# opamp_bandpass.net
KiCad netlist of a schematic drawn in EAGLE
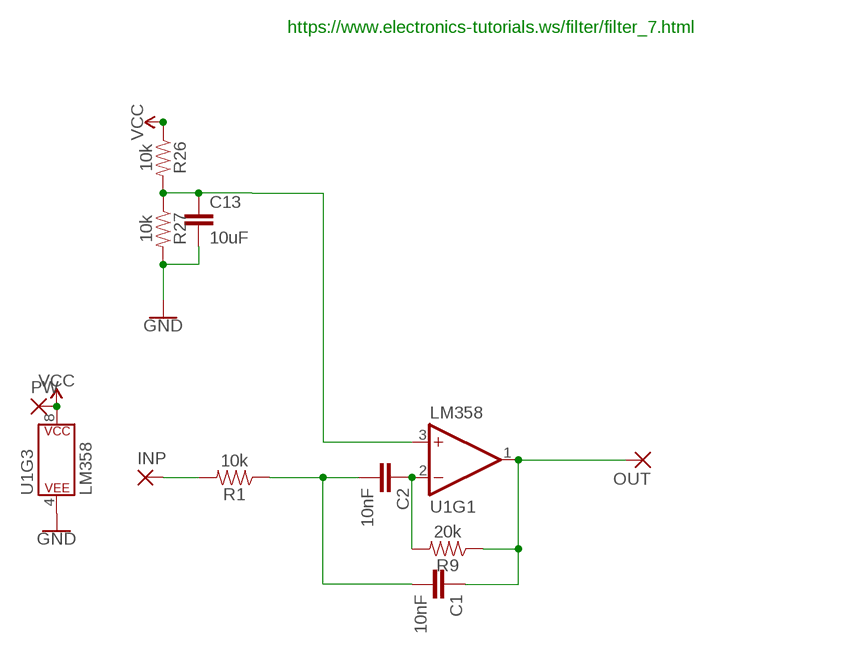
[diagram p0: schematic, sheet 1]

(export (version "E")
  (design (tool "Eeschema 10.0.6"))
  (components
    (comp (ref "C1")
      (value "10nF")
      (footprint "eagle-import:C5B3.5")
      (libsource (lib "eagle-import") (part "C5/3.5"))
    )
    (comp (ref "C2")
      (value "10nF")
      (footprint "eagle-import:C5B3.5")
      (libsource (lib "eagle-import") (part "C5/3.5"))
    )
    (comp (ref "C13")
      (value "10uF")
      (footprint "eagle-import:C5B3.5")
      (libsource (lib "eagle-import") (part "C5/3.5"))
    )
    (comp (ref "INP")
      (value "2,54/1,1")
      (footprint "eagle-import:2,54_1,1")
      (libsource (lib "eagle-import") (part "2,54/1,1"))
    )
    (comp (ref "OUT")
      (value "2,54/1,1")
      (footprint "eagle-import:2,54_1,1")
      (libsource (lib "eagle-import") (part "2,54/1,1"))
    )
    (comp (ref "PW")
      (value "2,54/1,1")
      (footprint "eagle-import:2,54_1,1")
      (libsource (lib "eagle-import") (part "2,54/1,1"))
    )
    (comp (ref "R1")
      (value "10k")
      (footprint "eagle-import:AXIAL-0.3")
      (libsource (lib "eagle-import") (part "1KOHM-HORIZ-1/4W-1%"))
    )
    (comp (ref "R9")
      (value "20k")
      (footprint "eagle-import:AXIAL-0.3")
      (libsource (lib "eagle-import") (part "1KOHM-HORIZ-1/4W-1%"))
    )
    (comp (ref "R26")
      (value "10k")
      (footprint "eagle-import:AXIAL-0.3")
      (libsource (lib "eagle-import") (part "1KOHM-HORIZ-1/4W-1%"))
    )
    (comp (ref "R27")
      (value "10k")
      (footprint "eagle-import:AXIAL-0.3")
      (libsource (lib "eagle-import") (part "1KOHM-HORIZ-1/4W-1%"))
    )
    (comp (ref "U1")
      (value "LM358")
      (footprint "eagle-import:DIP08")
      (libsource (lib "eagle-import") (part "LM358"))
    )
  )
  (nets
    (net (code "1") (name "GND") (class "Default")
      (node (ref "C13") (pin "2") (pinfunction "2_2") (pintype "passive"))
      (node (ref "R27") (pin "P$2") (pinfunction "2_P$2") (pintype "passive"))
      (node (ref "U1") (pin "4") (pinfunction "P$V-_4") (pintype "bidirectional"))
    )
    (net (code "2") (name "Net-(INP-P)") (class "Default")
      (node (ref "INP") (pin "1") (pinfunction "P_1") (pintype "passive"))
      (node (ref "R1") (pin "P$2") (pinfunction "2_P$2") (pintype "passive"))
    )
    (net (code "3") (name "Net-(OUT-P)") (class "Default")
      (node (ref "C1") (pin "1") (pinfunction "1_1") (pintype "passive"))
      (node (ref "OUT") (pin "1") (pinfunction "P_1") (pintype "passive"))
      (node (ref "R9") (pin "P$1") (pinfunction "1_P$1") (pintype "passive"))
      (node (ref "U1") (pin "1") (pinfunction "OUT_1") (pintype "output"))
    )
    (net (code "4") (name "Net-(R1-1)") (class "Default")
      (node (ref "C1") (pin "2") (pinfunction "2_2") (pintype "passive"))
      (node (ref "C2") (pin "2") (pinfunction "2_2") (pintype "passive"))
      (node (ref "R1") (pin "P$1") (pinfunction "1_P$1") (pintype "passive"))
    )
    (net (code "5") (name "Net-(R9-2)") (class "Default")
      (node (ref "C2") (pin "1") (pinfunction "1_1") (pintype "passive"))
      (node (ref "R9") (pin "P$2") (pinfunction "2_P$2") (pintype "passive"))
      (node (ref "U1") (pin "2") (pinfunction "-IN_2") (pintype "input"))
    )
    (net (code "6") (name "Net-(R26-2)") (class "Default")
      (node (ref "C13") (pin "1") (pinfunction "1_1") (pintype "passive"))
      (node (ref "R26") (pin "P$2") (pinfunction "2_P$2") (pintype "passive"))
      (node (ref "R27") (pin "P$1") (pinfunction "1_P$1") (pintype "passive"))
      (node (ref "U1") (pin "3") (pinfunction "+IN_3") (pintype "input"))
    )
    (net (code "7") (name "VCC") (class "Default")
      (node (ref "PW") (pin "1") (pinfunction "P_1") (pintype "passive"))
      (node (ref "R26") (pin "P$1") (pinfunction "1_P$1") (pintype "passive"))
      (node (ref "U1") (pin "8") (pinfunction "P$V+_8") (pintype "bidirectional"))
    )
  )
)
